# munia.net
KiCad netlist of a schematic drawn in EAGLE
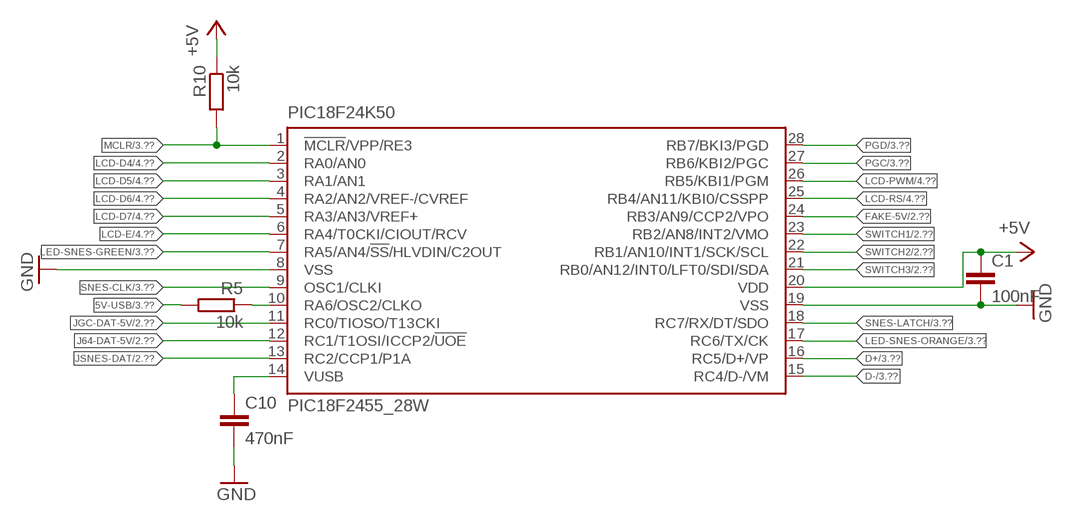
[diagram p0: schematic, sheet 1]
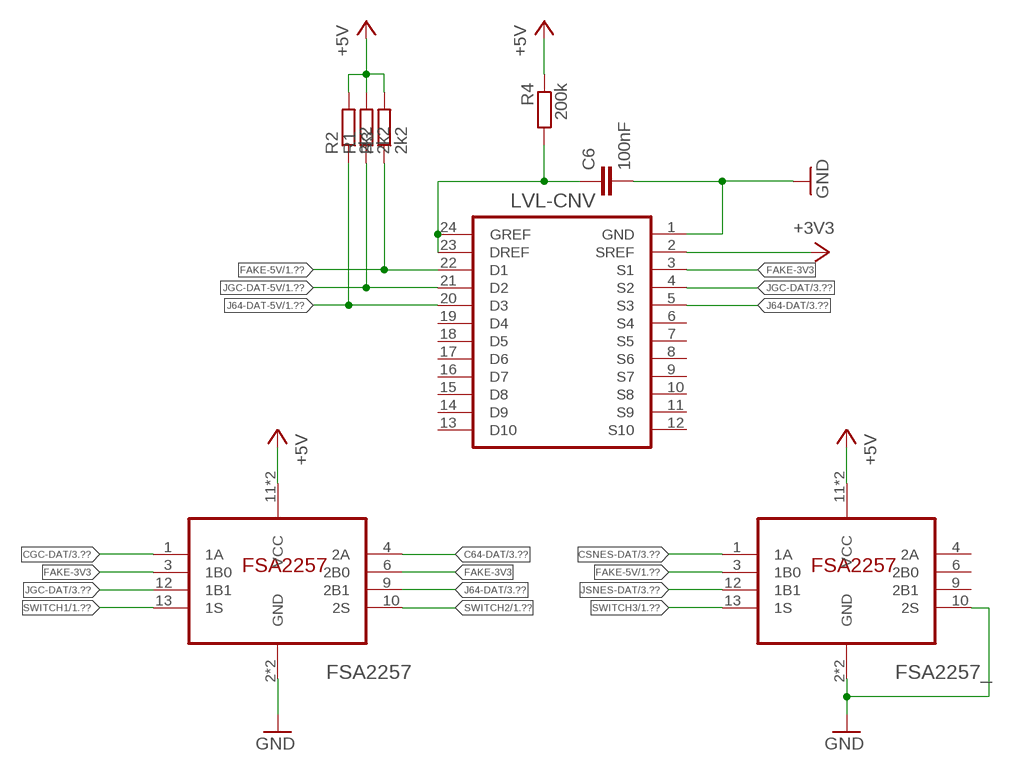
[diagram p1: schematic, sheet 2]
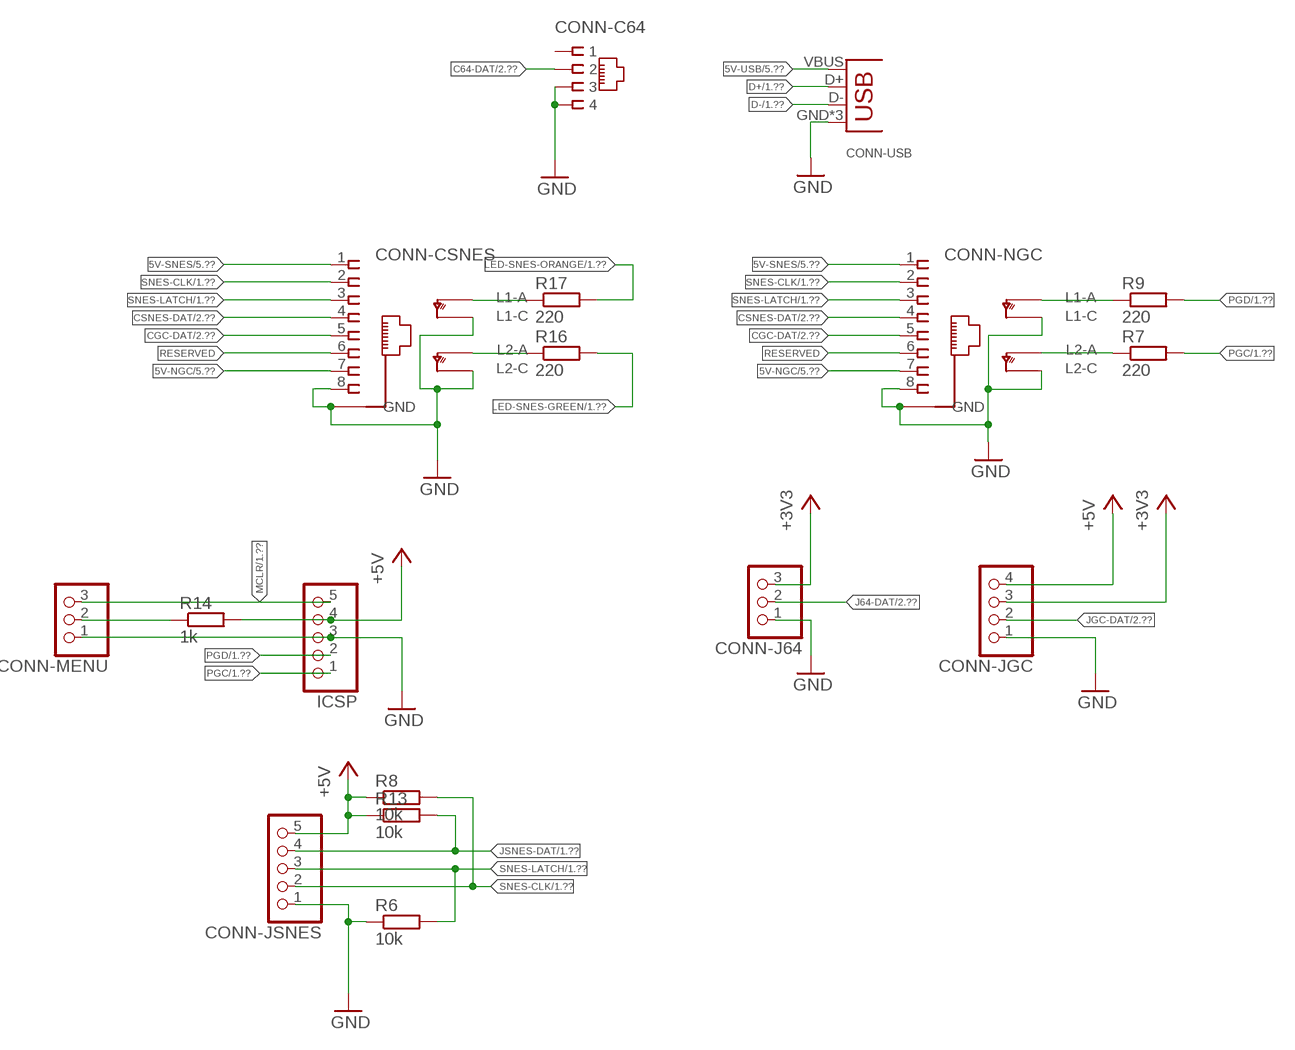
[diagram p2: schematic, sheet 3]
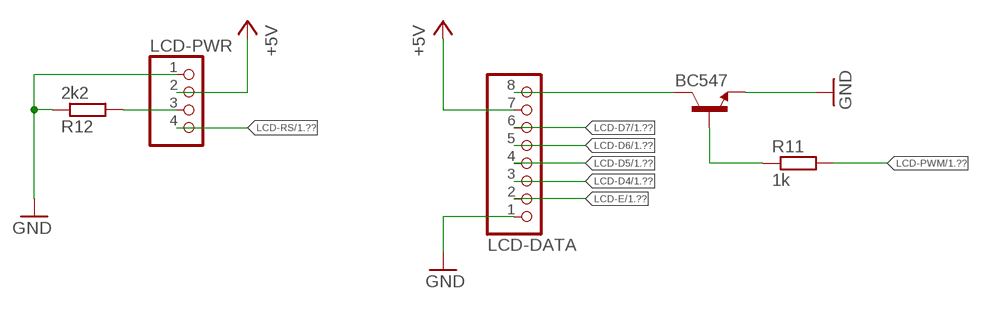
[diagram p3: schematic, sheet 4]
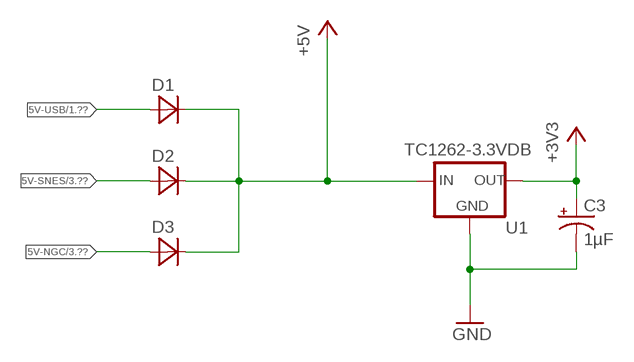
[diagram p4: schematic, sheet 5]

(export (version "E")
  (design (tool "Eeschema 10.0.6"))
  (components
    (comp (ref "C1")
      (value "100nF")
      (footprint "eagle-import:C0603")
      (libsource (lib "eagle-import") (part "C-EUC0603"))
    )
    (comp (ref "C10")
      (value "470nF")
      (footprint "eagle-import:C0603")
      (libsource (lib "eagle-import") (part "C-EUC0603"))
    )
    (comp (ref "PIC18F24K50")
      (value "PIC18F2455_28W")
      (footprint "eagle-import:SO28W")
      (fields (field (name "MF") "MICROCHIP") (field (name "MPN") "PIC18F2455-I/SO"))
      (libsource (lib "eagle-import") (part "PIC18F2_28W455"))
    )
    (comp (ref "R5")
      (value "10k")
      (footprint "eagle-import:R0603")
      (libsource (lib "eagle-import") (part "R-EU_R0603"))
    )
    (comp (ref "R10")
      (value "10k")
      (footprint "eagle-import:R0603")
      (libsource (lib "eagle-import") (part "R-EU_R0603"))
    )
    (comp (ref "C3")
      (value "1µF")
      (footprint "eagle-import:EIA3216")
      (libsource (lib "eagle-import") (part "TANT-CAP1206"))
    )
    (comp (ref "D1")
      (value "MBR120VLSFT1G")
      (footprint "eagle-import:SOD123")
      (libsource (lib "eagle-import") (part "MBR120VLSFT1G"))
    )
    (comp (ref "D2")
      (value "MBR120VLSFT1G")
      (footprint "eagle-import:SOD123")
      (libsource (lib "eagle-import") (part "MBR120VLSFT1G"))
    )
    (comp (ref "D3")
      (value "MBR120VLSFT1G")
      (footprint "eagle-import:SOD123")
      (libsource (lib "eagle-import") (part "MBR120VLSFT1G"))
    )
    (comp (ref "U1")
      (value "TC1262-3.3VDB")
      (footprint "eagle-import:SOT230P700X180-4N")
      (libsource (lib "eagle-import") (part "TC1262-3.3VDB"))
    )
    (comp (ref "CONN-C64")
      (value "RJ11-6P4C")
      (footprint "eagle-import:RJ11-4C")
      (libsource (lib "eagle-import") (part "RJ11-6P4C"))
    )
    (comp (ref "CONN-CSNES")
      (value "RJ45-NIELS")
      (footprint "eagle-import:RJ45-NIELS")
      (libsource (lib "eagle-import") (part "RJ45-NIELS"))
    )
    (comp (ref "CONN-J64")
      (value "PINHD-1X3")
      (footprint "eagle-import:1X03")
      (libsource (lib "eagle-import") (part "PINHD-1X3"))
    )
    (comp (ref "CONN-JGC")
      (value "PINHD-1X4")
      (footprint "eagle-import:1X04")
      (libsource (lib "eagle-import") (part "PINHD-1X4"))
    )
    (comp (ref "CONN-JSNES")
      (value "PINHD-1X5")
      (footprint "eagle-import:1X05")
      (libsource (lib "eagle-import") (part "PINHD-1X5"))
    )
    (comp (ref "CONN-MENU")
      (value "PINHD-1X3")
      (footprint "eagle-import:1X03")
      (libsource (lib "eagle-import") (part "PINHD-1X3"))
    )
    (comp (ref "CONN-NGC")
      (value "RJ45-NIELS")
      (footprint "eagle-import:RJ45-NIELS")
      (libsource (lib "eagle-import") (part "RJ45-NIELS"))
    )
    (comp (ref "CONN-USB")
      (value "USB-B-NIELS")
      (footprint "eagle-import:USB-B-H")
      (libsource (lib "eagle-import") (part "USB-B-NIELS"))
    )
    (comp (ref "ICSP")
      (value "PINHD-1X5")
      (footprint "eagle-import:1X05")
      (libsource (lib "eagle-import") (part "PINHD-1X5"))
    )
    (comp (ref "R6")
      (value "10k")
      (footprint "eagle-import:R0603")
      (libsource (lib "eagle-import") (part "R-EU_R0603"))
    )
    (comp (ref "R7")
      (value "220")
      (footprint "eagle-import:R0603")
      (libsource (lib "eagle-import") (part "R-EU_R0603"))
    )
    (comp (ref "R8")
      (value "10k")
      (footprint "eagle-import:R0603")
      (libsource (lib "eagle-import") (part "R-EU_R0603"))
    )
    (comp (ref "R9")
      (value "220")
      (footprint "eagle-import:R0603")
      (libsource (lib "eagle-import") (part "R-EU_R0603"))
    )
    (comp (ref "R13")
      (value "10k")
      (footprint "eagle-import:R0603")
      (libsource (lib "eagle-import") (part "R-EU_R0603"))
    )
    (comp (ref "R14")
      (value "1k")
      (footprint "eagle-import:R0603")
      (libsource (lib "eagle-import") (part "R-EU_R0603"))
    )
    (comp (ref "R16")
      (value "220")
      (footprint "eagle-import:R0603")
      (libsource (lib "eagle-import") (part "R-EU_R0603"))
    )
    (comp (ref "R17")
      (value "220")
      (footprint "eagle-import:R0603")
      (libsource (lib "eagle-import") (part "R-EU_R0603"))
    )
    (comp (ref "C6")
      (value "100nF")
      (footprint "eagle-import:C0603")
      (libsource (lib "eagle-import") (part "C-EUC0603"))
    )
    (comp (ref "FSA2257")
      (value "FSA2257MTCX")
      (footprint "eagle-import:TSSOP14")
      (libsource (lib "eagle-import") (part "FSA2257MTCX"))
    )
    (comp (ref "FSA2257_")
      (value "FSA2257MTCX")
      (footprint "eagle-import:TSSOP14")
      (libsource (lib "eagle-import") (part "FSA2257MTCX"))
    )
    (comp (ref "LVL-CNV")
      (value "GTL2010")
      (footprint "eagle-import:TSSOP24")
      (libsource (lib "eagle-import") (part "GTL2010"))
    )
    (comp (ref "R1")
      (value "2k2")
      (footprint "eagle-import:R0603")
      (libsource (lib "eagle-import") (part "R-EU_R0603"))
    )
    (comp (ref "R2")
      (value "2k2")
      (footprint "eagle-import:R0603")
      (libsource (lib "eagle-import") (part "R-EU_R0603"))
    )
    (comp (ref "R3")
      (value "2k2")
      (footprint "eagle-import:R0603")
      (libsource (lib "eagle-import") (part "R-EU_R0603"))
    )
    (comp (ref "R4")
      (value "200k")
      (footprint "eagle-import:R0603")
      (libsource (lib "eagle-import") (part "R-EU_R0603"))
    )
    (comp (ref "BC547")
      (value "BC847")
      (footprint "eagle-import:SOT23")
      (libsource (lib "eagle-import") (part "BC847"))
    )
    (comp (ref "LCD-DATA")
      (value "PINHD-1X8")
      (footprint "eagle-import:1X08")
      (libsource (lib "eagle-import") (part "PINHD-1X8"))
    )
    (comp (ref "LCD-PWR")
      (value "PINHD-1X4")
      (footprint "eagle-import:1X04")
      (libsource (lib "eagle-import") (part "PINHD-1X4"))
    )
    (comp (ref "R11")
      (value "1k")
      (footprint "eagle-import:R0603")
      (libsource (lib "eagle-import") (part "R-EU_R0603"))
    )
    (comp (ref "R12")
      (value "2k2")
      (footprint "eagle-import:R0603")
      (libsource (lib "eagle-import") (part "R-EU_R0603"))
    )
  )
  (nets
    (net (code "1") (name "+3V3") (class "Default")
      (node (ref "C3") (pin "A") (pinfunction "+_A") (pintype "passive"))
      (node (ref "CONN-J64") (pin "3") (pinfunction "3_3") (pintype "passive"))
      (node (ref "CONN-JGC") (pin "3") (pinfunction "3_3") (pintype "passive"))
      (node (ref "LVL-CNV") (pin "2") (pinfunction "SREF_2") (pintype "power_in"))
      (node (ref "U1") (pin "3") (pinfunction "OUT_3") (pintype "passive"))
    )
    (net (code "2") (name "+5V") (class "Default")
      (node (ref "C1") (pin "1") (pinfunction "1_1") (pintype "passive"))
      (node (ref "CONN-JGC") (pin "4") (pinfunction "4_4") (pintype "passive"))
      (node (ref "CONN-JSNES") (pin "5") (pinfunction "5_5") (pintype "passive"))
      (node (ref "D1") (pin "1") (pinfunction "C_1") (pintype "passive"))
      (node (ref "D2") (pin "1") (pinfunction "C_1") (pintype "passive"))
      (node (ref "D3") (pin "1") (pinfunction "C_1") (pintype "passive"))
      (node (ref "FSA2257") (pin "11") (pinfunction "VCC_11") (pintype "power_in"))
      (node (ref "FSA2257") (pin "14") (pinfunction "VCC_14") (pintype "power_in"))
      (node (ref "FSA2257_") (pin "11") (pinfunction "VCC_11") (pintype "power_in"))
      (node (ref "FSA2257_") (pin "14") (pinfunction "VCC_14") (pintype "power_in"))
      (node (ref "ICSP") (pin "4") (pinfunction "4_4") (pintype "passive"))
      (node (ref "LCD-DATA") (pin "7") (pinfunction "7_7") (pintype "passive"))
      (node (ref "LCD-PWR") (pin "2") (pinfunction "2_2") (pintype "passive"))
      (node (ref "PIC18F24K50") (pin "20") (pinfunction "VDD_20") (pintype "power_in"))
      (node (ref "R1") (pin "2") (pinfunction "2_2") (pintype "passive"))
      (node (ref "R10") (pin "1") (pinfunction "1_1") (pintype "passive"))
      (node (ref "R13") (pin "1") (pinfunction "1_1") (pintype "passive"))
      (node (ref "R14") (pin "2") (pinfunction "2_2") (pintype "passive"))
      (node (ref "R2") (pin "2") (pinfunction "2_2") (pintype "passive"))
      (node (ref "R3") (pin "2") (pinfunction "2_2") (pintype "passive"))
      (node (ref "R4") (pin "1") (pinfunction "1_1") (pintype "passive"))
      (node (ref "R8") (pin "1") (pinfunction "1_1") (pintype "passive"))
      (node (ref "U1") (pin "1") (pinfunction "IN_1") (pintype "input"))
    )
    (net (code "3") (name "5V-NGC") (class "Default")
      (node (ref "CONN-CSNES") (pin "7") (pinfunction "7_7") (pintype "passive"))
      (node (ref "CONN-NGC") (pin "7") (pinfunction "7_7") (pintype "passive"))
      (node (ref "D3") (pin "2") (pinfunction "A_2") (pintype "passive"))
    )
    (net (code "4") (name "5V-SNES") (class "Default")
      (node (ref "CONN-CSNES") (pin "1") (pinfunction "1_1") (pintype "passive"))
      (node (ref "CONN-NGC") (pin "1") (pinfunction "1_1") (pintype "passive"))
      (node (ref "D2") (pin "2") (pinfunction "A_2") (pintype "passive"))
    )
    (net (code "5") (name "5V-USB") (class "Default")
      (node (ref "CONN-USB") (pin "VBUS") (pinfunction "VBUS_VBUS") (pintype "bidirectional"))
      (node (ref "D1") (pin "2") (pinfunction "A_2") (pintype "passive"))
      (node (ref "R5") (pin "2") (pinfunction "2_2") (pintype "passive"))
    )
    (net (code "6") (name "C64-DAT") (class "Default")
      (node (ref "CONN-C64") (pin "2") (pinfunction "2_2") (pintype "passive"))
      (node (ref "FSA2257") (pin "4") (pinfunction "2A_4") (pintype "bidirectional"))
    )
    (net (code "7") (name "CGC-DAT") (class "Default")
      (node (ref "CONN-CSNES") (pin "5") (pinfunction "5_5") (pintype "passive"))
      (node (ref "CONN-NGC") (pin "5") (pinfunction "5_5") (pintype "passive"))
      (node (ref "FSA2257") (pin "1") (pinfunction "1A_1") (pintype "bidirectional"))
    )
    (net (code "8") (name "CSNES-DAT") (class "Default")
      (node (ref "CONN-CSNES") (pin "4") (pinfunction "4_4") (pintype "passive"))
      (node (ref "CONN-NGC") (pin "4") (pinfunction "4_4") (pintype "passive"))
      (node (ref "FSA2257_") (pin "1") (pinfunction "1A_1") (pintype "bidirectional"))
    )
    (net (code "9") (name "D+") (class "Default")
      (node (ref "CONN-USB") (pin "D+") (pinfunction "D+_D+") (pintype "bidirectional"))
      (node (ref "PIC18F24K50") (pin "16") (pinfunction "RC5/D+/VP_16") (pintype "bidirectional"))
    )
    (net (code "10") (name "D-") (class "Default")
      (node (ref "CONN-USB") (pin "D-") (pinfunction "D-_D-") (pintype "bidirectional"))
      (node (ref "PIC18F24K50") (pin "15") (pinfunction "RC4/D-/VM_15") (pintype "bidirectional"))
    )
    (net (code "11") (name "FAKE-3V3") (class "Default")
      (node (ref "FSA2257") (pin "3") (pinfunction "1B0_3") (pintype "bidirectional"))
      (node (ref "FSA2257") (pin "6") (pinfunction "2B0_6") (pintype "bidirectional"))
      (node (ref "LVL-CNV") (pin "3") (pinfunction "S1_3") (pintype "bidirectional"))
    )
    (net (code "12") (name "FAKE-5V") (class "Default")
      (node (ref "FSA2257_") (pin "3") (pinfunction "1B0_3") (pintype "bidirectional"))
      (node (ref "LVL-CNV") (pin "22") (pinfunction "D1_22") (pintype "bidirectional"))
      (node (ref "PIC18F24K50") (pin "24") (pinfunction "RB3/AN9/CCP2/VPO_24") (pintype "bidirectional"))
      (node (ref "R3") (pin "1") (pinfunction "1_1") (pintype "passive"))
    )
    (net (code "13") (name "GND") (class "Default")
      (node (ref "BC547") (pin "2") (pinfunction "E_2") (pintype "passive"))
      (node (ref "C1") (pin "2") (pinfunction "2_2") (pintype "passive"))
      (node (ref "C10") (pin "2") (pinfunction "2_2") (pintype "passive"))
      (node (ref "C3") (pin "C") (pinfunction "-_C") (pintype "passive"))
      (node (ref "C6") (pin "2") (pinfunction "2_2") (pintype "passive"))
      (node (ref "CONN-C64") (pin "3") (pinfunction "3_3") (pintype "passive"))
      (node (ref "CONN-C64") (pin "4") (pinfunction "4_4") (pintype "passive"))
      (node (ref "CONN-CSNES") (pin "8") (pinfunction "8_8") (pintype "passive"))
      (node (ref "CONN-CSNES") (pin "GND@5") (pinfunction "GND_GND@5") (pintype "power_in"))
      (node (ref "CONN-CSNES") (pin "GND@6") (pinfunction "GND_GND@6") (pintype "power_in"))
      (node (ref "CONN-CSNES") (pin "LED-GREEN-C") (pinfunction "L2C_LED-GREEN-C") (pintype "bidirectional"))
      (node (ref "CONN-CSNES") (pin "LED-ORANGE-C") (pinfunction "L1C_LED-ORANGE-C") (pintype "bidirectional"))
      (node (ref "CONN-J64") (pin "1") (pinfunction "1_1") (pintype "passive"))
      (node (ref "CONN-JGC") (pin "1") (pinfunction "1_1") (pintype "passive"))
      (node (ref "CONN-JSNES") (pin "1") (pinfunction "1_1") (pintype "passive"))
      (node (ref "CONN-MENU") (pin "1") (pinfunction "1_1") (pintype "passive"))
      (node (ref "CONN-NGC") (pin "8") (pinfunction "8_8") (pintype "passive"))
      (node (ref "CONN-NGC") (pin "GND@5") (pinfunction "GND_GND@5") (pintype "power_in"))
      (node (ref "CONN-NGC") (pin "GND@6") (pinfunction "GND_GND@6") (pintype "power_in"))
      (node (ref "CONN-NGC") (pin "LED-GREEN-C") (pinfunction "L2C_LED-GREEN-C") (pintype "bidirectional"))
      (node (ref "CONN-NGC") (pin "LED-ORANGE-C") (pinfunction "L1C_LED-ORANGE-C") (pintype "bidirectional"))
      (node (ref "CONN-USB") (pin "GND") (pinfunction "GND_GND") (pintype "bidirectional"))
      (node (ref "CONN-USB") (pin "GND@1") (pinfunction "GND_GND@1") (pintype "bidirectional"))
      (node (ref "CONN-USB") (pin "GND@2") (pinfunction "GND_GND@2") (pintype "bidirectional"))
      (node (ref "FSA2257") (pin "2") (pinfunction "GND_2") (pintype "power_in"))
      (node (ref "FSA2257") (pin "5") (pinfunction "GND_5") (pintype "power_in"))
      (node (ref "FSA2257_") (pin "10") (pinfunction "2S_10") (pintype "input"))
      (node (ref "FSA2257_") (pin "2") (pinfunction "GND_2") (pintype "power_in"))
      (node (ref "FSA2257_") (pin "5") (pinfunction "GND_5") (pintype "power_in"))
      (node (ref "ICSP") (pin "3") (pinfunction "3_3") (pintype "passive"))
      (node (ref "LCD-DATA") (pin "1") (pinfunction "1_1") (pintype "passive"))
      (node (ref "LCD-PWR") (pin "1") (pinfunction "1_1") (pintype "passive"))
      (node (ref "LVL-CNV") (pin "1") (pinfunction "GND_1") (pintype "power_in"))
      (node (ref "PIC18F24K50") (pin "19") (pinfunction "VSS_19") (pintype "power_in"))
      (node (ref "PIC18F24K50") (pin "8") (pinfunction "VSS_8") (pintype "power_in"))
      (node (ref "R12") (pin "1") (pinfunction "1_1") (pintype "passive"))
      (node (ref "R6") (pin "1") (pinfunction "1_1") (pintype "passive"))
      (node (ref "U1") (pin "2") (pinfunction "GND_2") (pintype "input"))
      (node (ref "U1") (pin "4") (pinfunction "GND_4") (pintype "input"))
    )
    (net (code "14") (name "J64-DAT") (class "Default")
      (node (ref "CONN-J64") (pin "2") (pinfunction "2_2") (pintype "passive"))
      (node (ref "FSA2257") (pin "9") (pinfunction "2B1_9") (pintype "bidirectional"))
      (node (ref "LVL-CNV") (pin "5") (pinfunction "S3_5") (pintype "bidirectional"))
    )
    (net (code "15") (name "J64-DAT-5V") (class "Default")
      (node (ref "LVL-CNV") (pin "20") (pinfunction "D3_20") (pintype "bidirectional"))
      (node (ref "PIC18F24K50") (pin "12") (pinfunction "RC1/T1OSI/ICCP2/~{UOE}_12") (pintype "bidirectional"))
      (node (ref "R2") (pin "1") (pinfunction "1_1") (pintype "passive"))
    )
    (net (code "16") (name "JGC-DAT") (class "Default")
      (node (ref "CONN-JGC") (pin "2") (pinfunction "2_2") (pintype "passive"))
      (node (ref "FSA2257") (pin "12") (pinfunction "1B1_12") (pintype "bidirectional"))
      (node (ref "LVL-CNV") (pin "4") (pinfunction "S2_4") (pintype "bidirectional"))
    )
    (net (code "17") (name "JGC-DAT-5V") (class "Default")
      (node (ref "LVL-CNV") (pin "21") (pinfunction "D2_21") (pintype "bidirectional"))
      (node (ref "PIC18F24K50") (pin "11") (pinfunction "RC0/TIOSO/T13CKI_11") (pintype "bidirectional"))
      (node (ref "R1") (pin "1") (pinfunction "1_1") (pintype "passive"))
    )
    (net (code "18") (name "JSNES-DAT") (class "Default")
      (node (ref "CONN-JSNES") (pin "4") (pinfunction "4_4") (pintype "passive"))
      (node (ref "FSA2257_") (pin "12") (pinfunction "1B1_12") (pintype "bidirectional"))
      (node (ref "PIC18F24K50") (pin "13") (pinfunction "RC2/CCP1/P1A_13") (pintype "bidirectional"))
      (node (ref "R13") (pin "2") (pinfunction "2_2") (pintype "passive"))
    )
    (net (code "19") (name "LCD-D4") (class "Default")
      (node (ref "LCD-DATA") (pin "3") (pinfunction "3_3") (pintype "passive"))
      (node (ref "PIC18F24K50") (pin "2") (pinfunction "RA0/AN0_2") (pintype "bidirectional"))
    )
    (net (code "20") (name "LCD-D5") (class "Default")
      (node (ref "LCD-DATA") (pin "4") (pinfunction "4_4") (pintype "passive"))
      (node (ref "PIC18F24K50") (pin "3") (pinfunction "RA1/AN1_3") (pintype "bidirectional"))
    )
    (net (code "21") (name "LCD-D6") (class "Default")
      (node (ref "LCD-DATA") (pin "5") (pinfunction "5_5") (pintype "passive"))
      (node (ref "PIC18F24K50") (pin "4") (pinfunction "RA2/AN2/VREF-/CVREF_4") (pintype "bidirectional"))
    )
    (net (code "22") (name "LCD-D7") (class "Default")
      (node (ref "LCD-DATA") (pin "6") (pinfunction "6_6") (pintype "passive"))
      (node (ref "PIC18F24K50") (pin "5") (pinfunction "RA3/AN3/VREF+_5") (pintype "bidirectional"))
    )
    (net (code "23") (name "LCD-E") (class "Default")
      (node (ref "LCD-DATA") (pin "2") (pinfunction "2_2") (pintype "passive"))
      (node (ref "PIC18F24K50") (pin "6") (pinfunction "RA4/T0CKI/CIOUT/RCV_6") (pintype "bidirectional"))
    )
    (net (code "24") (name "LCD-PWM") (class "Default")
      (node (ref "PIC18F24K50") (pin "26") (pinfunction "RB5/KBI1/PGM_26") (pintype "bidirectional"))
      (node (ref "R11") (pin "2") (pinfunction "2_2") (pintype "passive"))
    )
    (net (code "25") (name "LCD-RS") (class "Default")
      (node (ref "LCD-PWR") (pin "4") (pinfunction "4_4") (pintype "passive"))
      (node (ref "PIC18F24K50") (pin "25") (pinfunction "RB4/AN11/KBI0/CSSPP_25") (pintype "bidirectional"))
    )
    (net (code "26") (name "LED-SNES-GREEN") (class "Default")
      (node (ref "PIC18F24K50") (pin "7") (pinfunction "RA5/AN4/~{SS}/HLVDIN/C2OUT_7") (pintype "bidirectional"))
      (node (ref "R16") (pin "2") (pinfunction "2_2") (pintype "passive"))
    )
    (net (code "27") (name "LED-SNES-ORANGE") (class "Default")
      (node (ref "PIC18F24K50") (pin "17") (pinfunction "RC6/TX/CK_17") (pintype "bidirectional"))
      (node (ref "R17") (pin "2") (pinfunction "2_2") (pintype "passive"))
    )
    (net (code "28") (name "MCLR") (class "Default")
      (node (ref "CONN-MENU") (pin "3") (pinfunction "3_3") (pintype "passive"))
      (node (ref "ICSP") (pin "5") (pinfunction "5_5") (pintype "passive"))
      (node (ref "PIC18F24K50") (pin "1") (pinfunction "~{MCLR}/VPP/RE3_1") (pintype "input"))
      (node (ref "R10") (pin "2") (pinfunction "2_2") (pintype "passive"))
    )
    (net (code "29") (name "Net-(BC547-B)") (class "Default")
      (node (ref "BC547") (pin "1") (pinfunction "B_1") (pintype "passive"))
      (node (ref "R11") (pin "1") (pinfunction "1_1") (pintype "passive"))
    )
    (net (code "30") (name "Net-(BC547-C)") (class "Default")
      (node (ref "BC547") (pin "3") (pinfunction "C_3") (pintype "passive"))
      (node (ref "LCD-DATA") (pin "8") (pinfunction "8_8") (pintype "passive"))
    )
    (net (code "31") (name "Net-(CONN-CSNES-L1A)") (class "Default")
      (node (ref "CONN-CSNES") (pin "LED-ORANGE-A") (pinfunction "L1A_LED-ORANGE-A") (pintype "bidirectional"))
      (node (ref "R17") (pin "1") (pinfunction "1_1") (pintype "passive"))
    )
    (net (code "32") (name "Net-(CONN-CSNES-L2A)") (class "Default")
      (node (ref "CONN-CSNES") (pin "LED-GREEN-A") (pinfunction "L2A_LED-GREEN-A") (pintype "bidirectional"))
      (node (ref "R16") (pin "1") (pinfunction "1_1") (pintype "passive"))
    )
    (net (code "33") (name "Net-(CONN-MENU-Pad2)") (class "Default")
      (node (ref "CONN-MENU") (pin "2") (pinfunction "2_2") (pintype "passive"))
      (node (ref "R14") (pin "1") (pinfunction "1_1") (pintype "passive"))
    )
    (net (code "34") (name "Net-(CONN-NGC-L1A)") (class "Default")
      (node (ref "CONN-NGC") (pin "LED-ORANGE-A") (pinfunction "L1A_LED-ORANGE-A") (pintype "bidirectional"))
      (node (ref "R9") (pin "1") (pinfunction "1_1") (pintype "passive"))
    )
    (net (code "35") (name "Net-(CONN-NGC-L2A)") (class "Default")
      (node (ref "CONN-NGC") (pin "LED-GREEN-A") (pinfunction "L2A_LED-GREEN-A") (pintype "bidirectional"))
      (node (ref "R7") (pin "1") (pinfunction "1_1") (pintype "passive"))
    )
    (net (code "36") (name "Net-(LCD-PWR-Pad3)") (class "Default")
      (node (ref "LCD-PWR") (pin "3") (pinfunction "3_3") (pintype "passive"))
      (node (ref "R12") (pin "2") (pinfunction "2_2") (pintype "passive"))
    )
    (net (code "37") (name "Net-(LVL-CNV-DREF)") (class "Default")
      (node (ref "C6") (pin "1") (pinfunction "1_1") (pintype "passive"))
      (node (ref "LVL-CNV") (pin "23") (pinfunction "DREF_23") (pintype "power_in"))
      (node (ref "LVL-CNV") (pin "24") (pinfunction "GREF_24") (pintype "passive"))
      (node (ref "R4") (pin "2") (pinfunction "2_2") (pintype "passive"))
    )
    (net (code "38") (name "Net-(PIC18F24K50-RA6{slash}OSC2{slash}CLKO)") (class "Default")
      (node (ref "PIC18F24K50") (pin "10") (pinfunction "RA6/OSC2/CLKO_10") (pintype "output"))
      (node (ref "R5") (pin "1") (pinfunction "1_1") (pintype "passive"))
    )
    (net (code "39") (name "Net-(PIC18F24K50-VUSB)") (class "Default")
      (node (ref "C10") (pin "1") (pinfunction "1_1") (pintype "passive"))
      (node (ref "PIC18F24K50") (pin "14") (pinfunction "VUSB_14") (pintype "bidirectional"))
    )
    (net (code "40") (name "PGC") (class "Default")
      (node (ref "ICSP") (pin "1") (pinfunction "1_1") (pintype "passive"))
      (node (ref "PIC18F24K50") (pin "27") (pinfunction "RB6/KBI2/PGC_27") (pintype "bidirectional"))
      (node (ref "R7") (pin "2") (pinfunction "2_2") (pintype "passive"))
    )
    (net (code "41") (name "PGD") (class "Default")
      (node (ref "ICSP") (pin "2") (pinfunction "2_2") (pintype "passive"))
      (node (ref "PIC18F24K50") (pin "28") (pinfunction "RB7/BKI3/PGD_28") (pintype "bidirectional"))
      (node (ref "R9") (pin "2") (pinfunction "2_2") (pintype "passive"))
    )
    (net (code "42") (name "RESERVED") (class "Default")
      (node (ref "CONN-CSNES") (pin "6") (pinfunction "6_6") (pintype "passive"))
      (node (ref "CONN-NGC") (pin "6") (pinfunction "6_6") (pintype "passive"))
    )
    (net (code "43") (name "SNES-CLK") (class "Default")
      (node (ref "CONN-CSNES") (pin "2") (pinfunction "2_2") (pintype "passive"))
      (node (ref "CONN-JSNES") (pin "2") (pinfunction "2_2") (pintype "passive"))
      (node (ref "CONN-NGC") (pin "2") (pinfunction "2_2") (pintype "passive"))
      (node (ref "PIC18F24K50") (pin "9") (pinfunction "OSC1/CLKI_9") (pintype "input"))
      (node (ref "R8") (pin "2") (pinfunction "2_2") (pintype "passive"))
    )
    (net (code "44") (name "SNES-LATCH") (class "Default")
      (node (ref "CONN-CSNES") (pin "3") (pinfunction "3_3") (pintype "passive"))
      (node (ref "CONN-JSNES") (pin "3") (pinfunction "3_3") (pintype "passive"))
      (node (ref "CONN-NGC") (pin "3") (pinfunction "3_3") (pintype "passive"))
      (node (ref "PIC18F24K50") (pin "18") (pinfunction "RC7/RX/DT/SDO_18") (pintype "bidirectional"))
      (node (ref "R6") (pin "2") (pinfunction "2_2") (pintype "passive"))
    )
    (net (code "45") (name "SWITCH1") (class "Default")
      (node (ref "FSA2257") (pin "13") (pinfunction "1S_13") (pintype "input"))
      (node (ref "PIC18F24K50") (pin "23") (pinfunction "RB2/AN8/INT2/VMO_23") (pintype "bidirectional"))
    )
    (net (code "46") (name "SWITCH2") (class "Default")
      (node (ref "FSA2257") (pin "10") (pinfunction "2S_10") (pintype "input"))
      (node (ref "PIC18F24K50") (pin "22") (pinfunction "RB1/AN10/INT1/SCK/SCL_22") (pintype "bidirectional"))
    )
    (net (code "47") (name "SWITCH3") (class "Default")
      (node (ref "FSA2257_") (pin "13") (pinfunction "1S_13") (pintype "input"))
      (node (ref "PIC18F24K50") (pin "21") (pinfunction "RB0/AN12/INT0/LFT0/SDI/SDA_21") (pintype "bidirectional"))
    )
    (net (code "48") (name "unconnected-(CONN-C64-Pad1)") (class "Default")
      (node (ref "CONN-C64") (pin "1") (pinfunction "1_1") (pintype "passive"))
    )
    (net (code "49") (name "unconnected-(FSA2257_-2A-Pad4)") (class "Default")
      (node (ref "FSA2257_") (pin "4") (pinfunction "2A_4") (pintype "bidirectional"))
    )
    (net (code "50") (name "unconnected-(FSA2257_-2B0-Pad6)") (class "Default")
      (node (ref "FSA2257_") (pin "6") (pinfunction "2B0_6") (pintype "bidirectional"))
    )
    (net (code "51") (name "unconnected-(FSA2257_-2B1-Pad9)") (class "Default")
      (node (ref "FSA2257_") (pin "9") (pinfunction "2B1_9") (pintype "bidirectional"))
    )
    (net (code "52") (name "unconnected-(LVL-CNV-D4-Pad19)") (class "Default")
      (node (ref "LVL-CNV") (pin "19") (pinfunction "D4_19") (pintype "bidirectional"))
    )
    (net (code "53") (name "unconnected-(LVL-CNV-D5-Pad18)") (class "Default")
      (node (ref "LVL-CNV") (pin "18") (pinfunction "D5_18") (pintype "bidirectional"))
    )
    (net (code "54") (name "unconnected-(LVL-CNV-D6-Pad17)") (class "Default")
      (node (ref "LVL-CNV") (pin "17") (pinfunction "D6_17") (pintype "bidirectional"))
    )
    (net (code "55") (name "unconnected-(LVL-CNV-D7-Pad16)") (class "Default")
      (node (ref "LVL-CNV") (pin "16") (pinfunction "D7_16") (pintype "bidirectional"))
    )
    (net (code "56") (name "unconnected-(LVL-CNV-D8-Pad15)") (class "Default")
      (node (ref "LVL-CNV") (pin "15") (pinfunction "D8_15") (pintype "bidirectional"))
    )
    (net (code "57") (name "unconnected-(LVL-CNV-D9-Pad14)") (class "Default")
      (node (ref "LVL-CNV") (pin "14") (pinfunction "D9_14") (pintype "bidirectional"))
    )
    (net (code "58") (name "unconnected-(LVL-CNV-D10-Pad13)") (class "Default")
      (node (ref "LVL-CNV") (pin "13") (pinfunction "D10_13") (pintype "bidirectional"))
    )
    (net (code "59") (name "unconnected-(LVL-CNV-S4-Pad6)") (class "Default")
      (node (ref "LVL-CNV") (pin "6") (pinfunction "S4_6") (pintype "bidirectional"))
    )
    (net (code "60") (name "unconnected-(LVL-CNV-S5-Pad7)") (class "Default")
      (node (ref "LVL-CNV") (pin "7") (pinfunction "S5_7") (pintype "bidirectional"))
    )
    (net (code "61") (name "unconnected-(LVL-CNV-S6-Pad8)") (class "Default")
      (node (ref "LVL-CNV") (pin "8") (pinfunction "S6_8") (pintype "bidirectional"))
    )
    (net (code "62") (name "unconnected-(LVL-CNV-S7-Pad9)") (class "Default")
      (node (ref "LVL-CNV") (pin "9") (pinfunction "S7_9") (pintype "bidirectional"))
    )
    (net (code "63") (name "unconnected-(LVL-CNV-S8-Pad10)") (class "Default")
      (node (ref "LVL-CNV") (pin "10") (pinfunction "S8_10") (pintype "bidirectional"))
    )
    (net (code "64") (name "unconnected-(LVL-CNV-S9-Pad11)") (class "Default")
      (node (ref "LVL-CNV") (pin "11") (pinfunction "S9_11") (pintype "bidirectional"))
    )
    (net (code "65") (name "unconnected-(LVL-CNV-S10-Pad12)") (class "Default")
      (node (ref "LVL-CNV") (pin "12") (pinfunction "S10_12") (pintype "bidirectional"))
    )
  )
)
